# design.net
KiCad netlist of a schematic drawn in Altium Designer
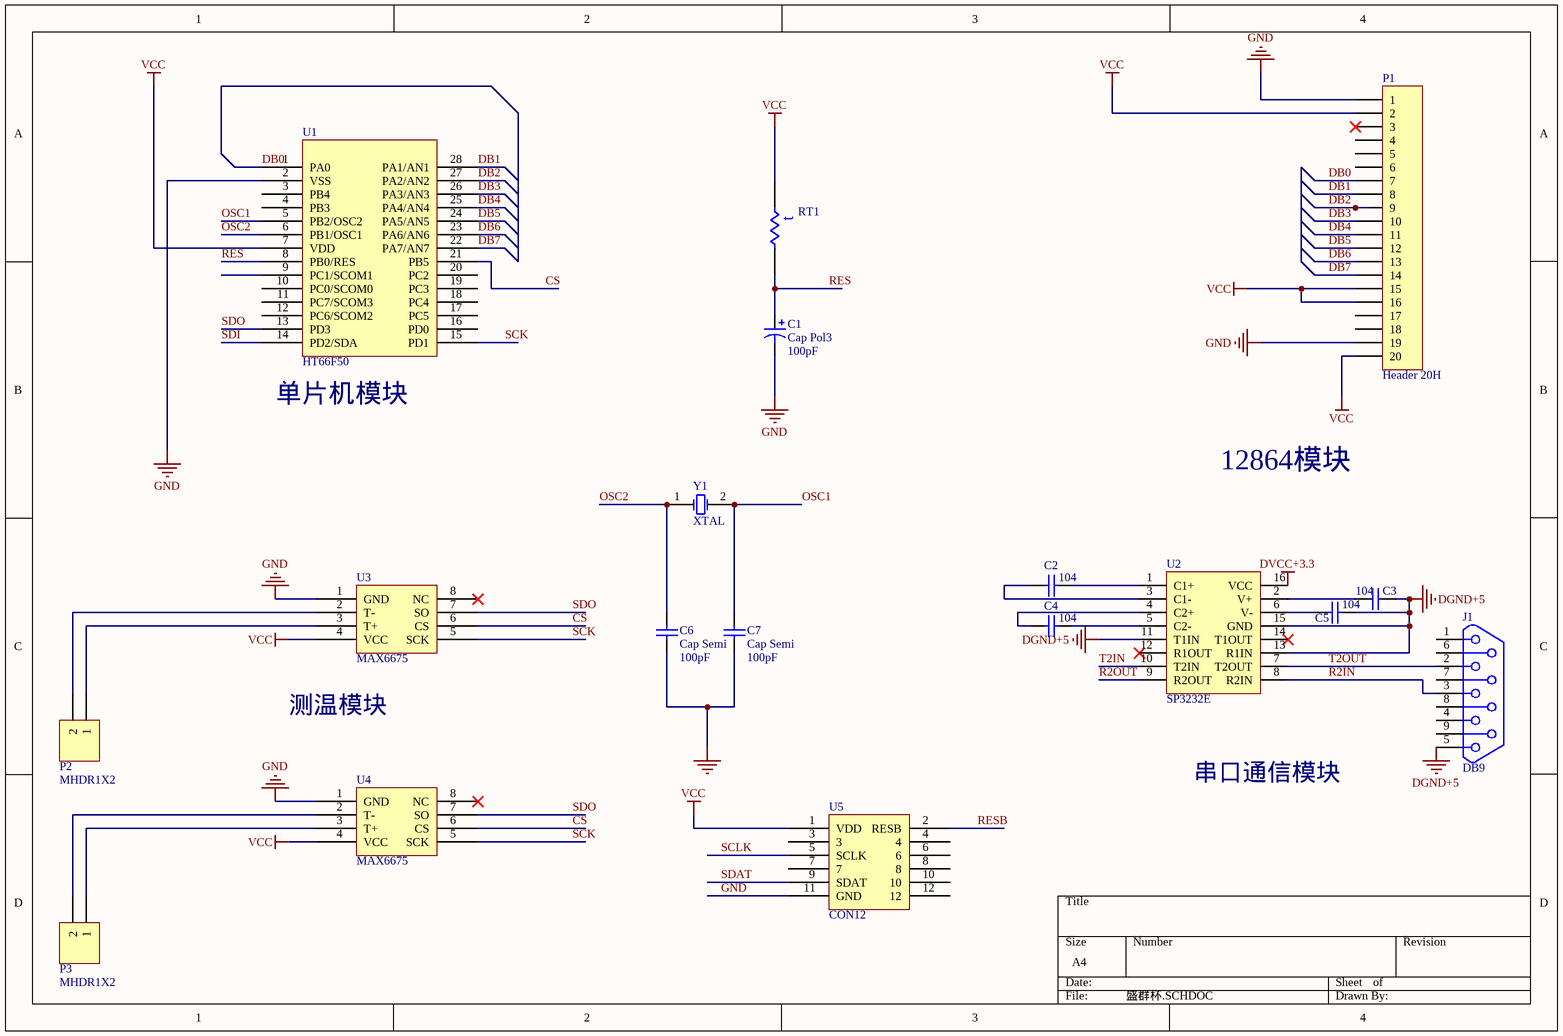
[diagram p0: 盛群杯.SCHDOC]

(export (version "E")
  (design (tool "Eeschema 10.0.6"))
  (components
    (comp (ref "C1")
      (value "Cap Pol3")
      (footprint "C0805")
      (description "Polarized Capacitor (Surface Mount)")
      (fields (field (name "ALTIUM_VALUE") "100pF") (field (name "PUBLISHER") "Altium Limited"))
      (libsource (lib "Miscellaneous Devices") (part "Cap Pol3"))
    )
    (comp (ref "C2")
      (value "104")
      (footprint "0805")
      (description "Capacitor")
      (fields (field (name "Comment") "Cap") (field (name "PUBLISHER") "Altium Limited"))
      (libsource (lib "自制Miscellaneous Devices库") (part "Cap"))
    )
    (comp (ref "C3")
      (value "104")
      (footprint "0805")
      (description "Capacitor")
      (fields (field (name "Comment") "Cap") (field (name "PUBLISHER") "Altium Limited"))
      (libsource (lib "自制Miscellaneous Devices库") (part "Cap"))
    )
    (comp (ref "C4")
      (value "104")
      (footprint "0805")
      (description "Capacitor")
      (fields (field (name "Comment") "Cap") (field (name "PUBLISHER") "Altium Limited"))
      (libsource (lib "自制Miscellaneous Devices库") (part "Cap"))
    )
    (comp (ref "C5")
      (value "104")
      (footprint "0805")
      (description "Capacitor")
      (fields (field (name "Comment") "Cap") (field (name "PUBLISHER") "Altium Limited"))
      (libsource (lib "自制Miscellaneous Devices库") (part "Cap"))
    )
    (comp (ref "C6")
      (value "Cap Semi")
      (footprint "1608[0603]")
      (description "Capacitor (Semiconductor SIM Model)")
      (fields (field (name "ALTIUM_VALUE") "100pF") (field (name "PUBLISHER") "Altium Limited"))
      (libsource (lib "Miscellaneous Devices") (part "Cap Semi"))
    )
    (comp (ref "C7")
      (value "Cap Semi")
      (footprint "1608[0603]")
      (description "Capacitor (Semiconductor SIM Model)")
      (fields (field (name "ALTIUM_VALUE") "100pF") (field (name "PUBLISHER") "Altium Limited"))
      (libsource (lib "Miscellaneous Devices") (part "Cap Semi"))
    )
    (comp (ref "J1") (value "DB9") (footprint "DB_9") (libsource (lib "mySCHlib") (part "DB9")))
    (comp (ref "P1")
      (value "Header 20H")
      (footprint "HDR1X20")
      (description "Header, 20-Pin, Right Angle")
      (fields (field (name "PUBLISHER") "Altium Limited"))
      (libsource (lib "Miscellaneous Connectors") (part "Header 20H"))
    )
    (comp (ref "P2")
      (value "MHDR1X2")
      (footprint "PCBComponent_1")
      (description "Header, 2-Pin")
      (fields (field (name "PUBLISHER") "Altium Limited"))
      (libsource (lib "Miscellaneous Connectors") (part "MHDR1X2"))
    )
    (comp (ref "P3")
      (value "MHDR1X2")
      (footprint "PCBComponent_1")
      (description "Header, 2-Pin")
      (fields (field (name "PUBLISHER") "Altium Limited"))
      (libsource (lib "Miscellaneous Connectors") (part "MHDR1X2"))
    )
    (comp (ref "RT1")
      (value "~")
      (footprint "6-0805")
      (description "Thermistor")
      (fields (field (name "PUBLISHER") "Altium Limited"))
      (libsource (lib "Miscellaneous Devices") (part "Res Thermal"))
    )
    (comp (ref "U1") (value "HT66F50") (libsource (lib "LIC") (part "HT66F50")))
    (comp (ref "U2") (value "SP3232E") (libsource (lib "自制原理图元件库") (part "SP3232E")))
    (comp (ref "U3") (value "MAX6675") (libsource (lib "LIC") (part "MAX6675")))
    (comp (ref "U4") (value "MAX6675") (libsource (lib "LIC") (part "MAX6675")))
    (comp (ref "U5") (value "CON12") (footprint "MHDR2X6") (libsource (lib "LIC") (part "CON12")))
    (comp (ref "Y1")
      (value "XTAL")
      (footprint "R38")
      (description "Crystal Oscillator")
      (fields (field (name "PUBLISHER") "Altium Limited"))
      (libsource (lib "Miscellaneous Devices") (part "XTAL"))
    )
  )
  (nets
    (net (code "1") (name "/CS") (class "Default")
      (node (ref "U1") (pin "21") (pinfunction "PB5_21") (pintype "passive"))
      (node (ref "U3") (pin "6") (pinfunction "CS_6") (pintype "passive"))
      (node (ref "U4") (pin "6") (pinfunction "CS_6") (pintype "passive"))
    )
    (net (code "2") (name "/DB0") (class "Default")
      (node (ref "P1") (pin "7") (pinfunction "7_7") (pintype "passive"))
      (node (ref "U1") (pin "1") (pinfunction "PA0_1") (pintype "passive"))
    )
    (net (code "3") (name "/DB1") (class "Default")
      (node (ref "P1") (pin "8") (pinfunction "8_8") (pintype "passive"))
      (node (ref "U1") (pin "28") (pinfunction "PA1/AN1_28") (pintype "passive"))
    )
    (net (code "4") (name "/DB2") (class "Default")
      (node (ref "P1") (pin "9") (pinfunction "9_9") (pintype "passive"))
      (node (ref "U1") (pin "27") (pinfunction "PA2/AN2_27") (pintype "passive"))
    )
    (net (code "5") (name "/DB3") (class "Default")
      (node (ref "P1") (pin "10") (pinfunction "10_10") (pintype "passive"))
      (node (ref "U1") (pin "26") (pinfunction "PA3/AN3_26") (pintype "passive"))
    )
    (net (code "6") (name "/DB4") (class "Default")
      (node (ref "P1") (pin "11") (pinfunction "11_11") (pintype "passive"))
      (node (ref "U1") (pin "25") (pinfunction "PA4/AN4_25") (pintype "passive"))
    )
    (net (code "7") (name "/DB5") (class "Default")
      (node (ref "P1") (pin "12") (pinfunction "12_12") (pintype "passive"))
      (node (ref "U1") (pin "24") (pinfunction "PA5/AN5_24") (pintype "passive"))
    )
    (net (code "8") (name "/DB6") (class "Default")
      (node (ref "P1") (pin "13") (pinfunction "13_13") (pintype "passive"))
      (node (ref "U1") (pin "23") (pinfunction "PA6/AN6_23") (pintype "passive"))
    )
    (net (code "9") (name "/DB7") (class "Default")
      (node (ref "P1") (pin "14") (pinfunction "14_14") (pintype "passive"))
      (node (ref "U1") (pin "22") (pinfunction "PA7/AN7_22") (pintype "passive"))
    )
    (net (code "10") (name "/OSC1") (class "Default")
      (node (ref "C7") (pin "1") (pinfunction "1_1") (pintype "passive"))
      (node (ref "U1") (pin "5") (pinfunction "PB2/OSC2_5") (pintype "passive"))
      (node (ref "Y1") (pin "2") (pinfunction "OSC2_2") (pintype "passive"))
    )
    (net (code "11") (name "/OSC2") (class "Default")
      (node (ref "C6") (pin "1") (pinfunction "1_1") (pintype "passive"))
      (node (ref "U1") (pin "6") (pinfunction "PB1/OSC1_6") (pintype "passive"))
      (node (ref "Y1") (pin "1") (pinfunction "OSC1_1") (pintype "passive"))
    )
    (net (code "12") (name "/R2IN") (class "Default")
      (node (ref "J1") (pin "3") (pinfunction "3_3") (pintype "passive"))
      (node (ref "U2") (pin "8") (pinfunction "R2IN_8") (pintype "passive"))
    )
    (net (code "13") (name "/R2OUT") (class "Default")
      (node (ref "U2") (pin "9") (pinfunction "R2OUT_9") (pintype "passive"))
    )
    (net (code "14") (name "/RES") (class "Default")
      (node (ref "C1") (pin "1") (pinfunction "1_1") (pintype "passive"))
      (node (ref "RT1") (pin "2") (pinfunction "2_2") (pintype "passive"))
      (node (ref "U1") (pin "8") (pinfunction "PB0/RES_8") (pintype "passive"))
    )
    (net (code "15") (name "/RESB") (class "Default")
      (node (ref "U5") (pin "2") (pinfunction "RESB_2") (pintype "passive"))
    )
    (net (code "16") (name "/SCK") (class "Default")
      (node (ref "U1") (pin "15") (pinfunction "PD1_15") (pintype "passive"))
      (node (ref "U3") (pin "5") (pinfunction "SCK_5") (pintype "passive"))
      (node (ref "U4") (pin "5") (pinfunction "SCK_5") (pintype "passive"))
    )
    (net (code "17") (name "/SCLK") (class "Default")
      (node (ref "U5") (pin "5") (pinfunction "SCLK_5") (pintype "passive"))
    )
    (net (code "18") (name "/SDAT") (class "Default")
      (node (ref "U5") (pin "9") (pinfunction "SDAT_9") (pintype "passive"))
    )
    (net (code "19") (name "/SDI") (class "Default")
      (node (ref "U1") (pin "14") (pinfunction "PD2/SDA_14") (pintype "passive"))
    )
    (net (code "20") (name "/SDO") (class "Default")
      (node (ref "U1") (pin "13") (pinfunction "PD3_13") (pintype "passive"))
      (node (ref "U3") (pin "7") (pinfunction "SO_7") (pintype "passive"))
      (node (ref "U4") (pin "7") (pinfunction "SO_7") (pintype "passive"))
    )
    (net (code "21") (name "/T2IN") (class "Default")
      (node (ref "U2") (pin "10") (pinfunction "T2IN_10") (pintype "passive"))
    )
    (net (code "22") (name "/T2OUT") (class "Default")
      (node (ref "J1") (pin "2") (pinfunction "2_2") (pintype "passive"))
      (node (ref "U2") (pin "7") (pinfunction "T2OUT_7") (pintype "passive"))
    )
    (net (code "23") (name "DGND+5") (class "Default")
      (node (ref "C3") (pin "2") (pinfunction "2_2") (pintype "passive"))
      (node (ref "C5") (pin "2") (pinfunction "2_2") (pintype "passive"))
      (node (ref "J1") (pin "5") (pinfunction "5_5") (pintype "passive"))
      (node (ref "U2") (pin "11") (pinfunction "T1IN_11") (pintype "passive"))
      (node (ref "U2") (pin "13") (pinfunction "R1IN_13") (pintype "passive"))
      (node (ref "U2") (pin "15") (pinfunction "GND_15") (pintype "passive"))
    )
    (net (code "24") (name "DVCC+3.3") (class "Default")
      (node (ref "U2") (pin "16") (pinfunction "VCC_16") (pintype "passive"))
    )
    (net (code "25") (name "GND") (class "Default")
      (node (ref "C1") (pin "2") (pinfunction "2_2") (pintype "passive"))
      (node (ref "C6") (pin "2") (pinfunction "2_2") (pintype "passive"))
      (node (ref "C7") (pin "2") (pinfunction "2_2") (pintype "passive"))
      (node (ref "P1") (pin "1") (pinfunction "1_1") (pintype "passive"))
      (node (ref "P1") (pin "19") (pinfunction "19_19") (pintype "passive"))
      (node (ref "U1") (pin "2") (pinfunction "VSS_2") (pintype "passive"))
      (node (ref "U3") (pin "1") (pinfunction "GND_1") (pintype "passive"))
      (node (ref "U4") (pin "1") (pinfunction "GND_1") (pintype "passive"))
      (node (ref "U5") (pin "11") (pinfunction "GND_11") (pintype "passive"))
    )
    (net (code "26") (name "Net-(U2-C1+)") (class "Default")
      (node (ref "C2") (pin "2") (pinfunction "2_2") (pintype "passive"))
      (node (ref "U2") (pin "1") (pinfunction "C1+_1") (pintype "passive"))
    )
    (net (code "27") (name "Net-(U2-C1-)") (class "Default")
      (node (ref "C2") (pin "1") (pinfunction "1_1") (pintype "passive"))
      (node (ref "U2") (pin "3") (pinfunction "C1-_3") (pintype "passive"))
    )
    (net (code "28") (name "Net-(U2-C2+)") (class "Default")
      (node (ref "C4") (pin "1") (pinfunction "1_1") (pintype "passive"))
      (node (ref "U2") (pin "4") (pinfunction "C2+_4") (pintype "passive"))
    )
    (net (code "29") (name "Net-(U2-C2-)") (class "Default")
      (node (ref "C4") (pin "2") (pinfunction "2_2") (pintype "passive"))
      (node (ref "U2") (pin "5") (pinfunction "C2-_5") (pintype "passive"))
    )
    (net (code "30") (name "Net-(U2-V+)") (class "Default")
      (node (ref "C3") (pin "1") (pinfunction "1_1") (pintype "passive"))
      (node (ref "U2") (pin "2") (pinfunction "V+_2") (pintype "passive"))
    )
    (net (code "31") (name "Net-(U2-V-)") (class "Default")
      (node (ref "C5") (pin "1") (pinfunction "1_1") (pintype "passive"))
      (node (ref "U2") (pin "6") (pinfunction "V-_6") (pintype "passive"))
    )
    (net (code "32") (name "Net-(U3-T+)") (class "Default")
      (node (ref "P2") (pin "1") (pinfunction "1_1") (pintype "passive"))
      (node (ref "U3") (pin "3") (pinfunction "T+_3") (pintype "passive"))
    )
    (net (code "33") (name "Net-(U3-T-)") (class "Default")
      (node (ref "P2") (pin "2") (pinfunction "2_2") (pintype "passive"))
      (node (ref "U3") (pin "2") (pinfunction "T-_2") (pintype "passive"))
    )
    (net (code "34") (name "Net-(U4-T+)") (class "Default")
      (node (ref "P3") (pin "1") (pinfunction "1_1") (pintype "passive"))
      (node (ref "U4") (pin "3") (pinfunction "T+_3") (pintype "passive"))
    )
    (net (code "35") (name "Net-(U4-T-)") (class "Default")
      (node (ref "P3") (pin "2") (pinfunction "2_2") (pintype "passive"))
      (node (ref "U4") (pin "2") (pinfunction "T-_2") (pintype "passive"))
    )
    (net (code "36") (name "VCC") (class "Default")
      (node (ref "P1") (pin "15") (pinfunction "15_15") (pintype "passive"))
      (node (ref "P1") (pin "16") (pinfunction "16_16") (pintype "passive"))
      (node (ref "P1") (pin "2") (pinfunction "2_2") (pintype "passive"))
      (node (ref "P1") (pin "20") (pinfunction "20_20") (pintype "passive"))
      (node (ref "RT1") (pin "1") (pinfunction "1_1") (pintype "passive"))
      (node (ref "U1") (pin "7") (pinfunction "VDD_7") (pintype "passive"))
      (node (ref "U3") (pin "4") (pinfunction "VCC_4") (pintype "passive"))
      (node (ref "U4") (pin "4") (pinfunction "VCC_4") (pintype "passive"))
      (node (ref "U5") (pin "1") (pinfunction "VDD_1") (pintype "passive"))
    )
    (net (code "37") (name "unconnected-(J1-Pad1)") (class "Default")
      (node (ref "J1") (pin "1") (pinfunction "1_1") (pintype "passive"))
    )
    (net (code "38") (name "unconnected-(J1-Pad4)") (class "Default")
      (node (ref "J1") (pin "4") (pinfunction "4_4") (pintype "passive"))
    )
    (net (code "39") (name "unconnected-(J1-Pad6)") (class "Default")
      (node (ref "J1") (pin "6") (pinfunction "6_6") (pintype "passive"))
    )
    (net (code "40") (name "unconnected-(J1-Pad7)") (class "Default")
      (node (ref "J1") (pin "7") (pinfunction "7_7") (pintype "passive"))
    )
    (net (code "41") (name "unconnected-(J1-Pad8)") (class "Default")
      (node (ref "J1") (pin "8") (pinfunction "8_8") (pintype "passive"))
    )
    (net (code "42") (name "unconnected-(J1-Pad9)") (class "Default")
      (node (ref "J1") (pin "9") (pinfunction "9_9") (pintype "passive"))
    )
    (net (code "43") (name "unconnected-(P1-Pad3)") (class "Default")
      (node (ref "P1") (pin "3") (pinfunction "3_3") (pintype "passive+no_connect"))
    )
    (net (code "44") (name "unconnected-(P1-Pad4)") (class "Default")
      (node (ref "P1") (pin "4") (pinfunction "4_4") (pintype "passive"))
    )
    (net (code "45") (name "unconnected-(P1-Pad5)") (class "Default")
      (node (ref "P1") (pin "5") (pinfunction "5_5") (pintype "passive"))
    )
    (net (code "46") (name "unconnected-(P1-Pad6)") (class "Default")
      (node (ref "P1") (pin "6") (pinfunction "6_6") (pintype "passive"))
    )
    (net (code "47") (name "unconnected-(P1-Pad17)") (class "Default")
      (node (ref "P1") (pin "17") (pinfunction "17_17") (pintype "passive"))
    )
    (net (code "48") (name "unconnected-(P1-Pad18)") (class "Default")
      (node (ref "P1") (pin "18") (pinfunction "18_18") (pintype "passive"))
    )
    (net (code "49") (name "unconnected-(U1-PB3-Pad4)") (class "Default")
      (node (ref "U1") (pin "4") (pinfunction "PB3_4") (pintype "passive"))
    )
    (net (code "50") (name "unconnected-(U1-PB4-Pad3)") (class "Default")
      (node (ref "U1") (pin "3") (pinfunction "PB4_3") (pintype "passive"))
    )
    (net (code "51") (name "unconnected-(U1-PC0{slash}SCOM0-Pad10)") (class "Default")
      (node (ref "U1") (pin "10") (pinfunction "PC0/SCOM0_10") (pintype "passive"))
    )
    (net (code "52") (name "unconnected-(U1-PC1{slash}SCOM1-Pad9)") (class "Default")
      (node (ref "U1") (pin "9") (pinfunction "PC1/SCOM1_9") (pintype "passive"))
    )
    (net (code "53") (name "unconnected-(U1-PC2-Pad20)") (class "Default")
      (node (ref "U1") (pin "20") (pinfunction "PC2_20") (pintype "passive"))
    )
    (net (code "54") (name "unconnected-(U1-PC3-Pad19)") (class "Default")
      (node (ref "U1") (pin "19") (pinfunction "PC3_19") (pintype "passive"))
    )
    (net (code "55") (name "unconnected-(U1-PC4-Pad18)") (class "Default")
      (node (ref "U1") (pin "18") (pinfunction "PC4_18") (pintype "passive"))
    )
    (net (code "56") (name "unconnected-(U1-PC5-Pad17)") (class "Default")
      (node (ref "U1") (pin "17") (pinfunction "PC5_17") (pintype "passive"))
    )
    (net (code "57") (name "unconnected-(U1-PC6{slash}SCOM2-Pad12)") (class "Default")
      (node (ref "U1") (pin "12") (pinfunction "PC6/SCOM2_12") (pintype "passive"))
    )
    (net (code "58") (name "unconnected-(U1-PC7{slash}SCOM3-Pad11)") (class "Default")
      (node (ref "U1") (pin "11") (pinfunction "PC7/SCOM3_11") (pintype "passive"))
    )
    (net (code "59") (name "unconnected-(U1-PD0-Pad16)") (class "Default")
      (node (ref "U1") (pin "16") (pinfunction "PD0_16") (pintype "passive"))
    )
    (net (code "60") (name "unconnected-(U2-R1OUT-Pad12)") (class "Default")
      (node (ref "U2") (pin "12") (pinfunction "R1OUT_12") (pintype "passive+no_connect"))
    )
    (net (code "61") (name "unconnected-(U2-T1OUT-Pad14)") (class "Default")
      (node (ref "U2") (pin "14") (pinfunction "T1OUT_14") (pintype "passive+no_connect"))
    )
    (net (code "62") (name "unconnected-(U3-NC-Pad8)") (class "Default")
      (node (ref "U3") (pin "8") (pinfunction "NC_8") (pintype "passive+no_connect"))
    )
    (net (code "63") (name "unconnected-(U4-NC-Pad8)") (class "Default")
      (node (ref "U4") (pin "8") (pinfunction "NC_8") (pintype "passive+no_connect"))
    )
    (net (code "64") (name "unconnected-(U5-Pad3)") (class "Default")
      (node (ref "U5") (pin "3") (pinfunction "3_3") (pintype "passive"))
    )
    (net (code "65") (name "unconnected-(U5-Pad4)") (class "Default")
      (node (ref "U5") (pin "4") (pinfunction "4_4") (pintype "passive"))
    )
    (net (code "66") (name "unconnected-(U5-Pad6)") (class "Default")
      (node (ref "U5") (pin "6") (pinfunction "6_6") (pintype "passive"))
    )
    (net (code "67") (name "unconnected-(U5-Pad7)") (class "Default")
      (node (ref "U5") (pin "7") (pinfunction "7_7") (pintype "passive"))
    )
    (net (code "68") (name "unconnected-(U5-Pad8)") (class "Default")
      (node (ref "U5") (pin "8") (pinfunction "8_8") (pintype "passive"))
    )
    (net (code "69") (name "unconnected-(U5-Pad10)") (class "Default")
      (node (ref "U5") (pin "10") (pinfunction "10_10") (pintype "passive"))
    )
    (net (code "70") (name "unconnected-(U5-Pad12)") (class "Default")
      (node (ref "U5") (pin "12") (pinfunction "12_12") (pintype "passive"))
    )
  )
)
